# 02_CPU_1214c.net
KiCad netlist of a schematic drawn in Altium Designer
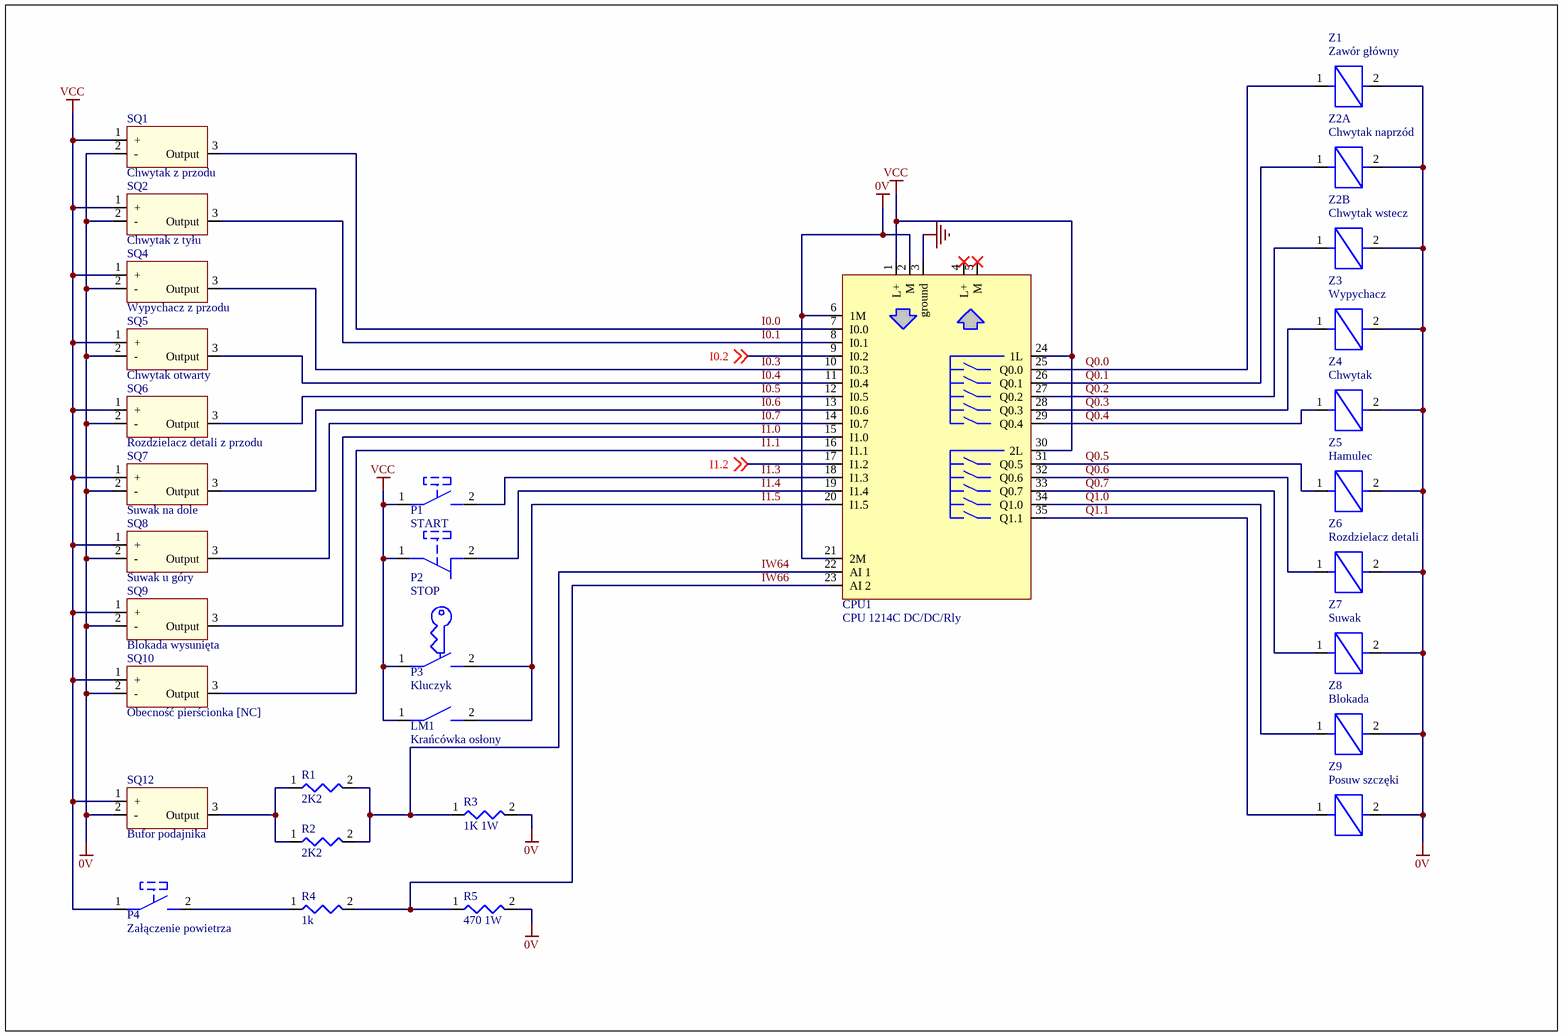
[diagram p0: [02] CPU 1214c.SchDoc]

(export (version "E")
  (design (tool "Eeschema 10.0.6"))
  (components
    (comp (ref "CPU1") (value "CPU 1214C DC/DC/Rly") (libsource (lib "Schlib2") (part "CPU 1214C DC/DC/Rly")))
    (comp (ref "LM1") (value "Krańcówka osłony") (libsource (lib "Schlib2") (part "NO")))
    (comp (ref "P1") (value "START") (libsource (lib "Schlib2") (part "Button NO")))
    (comp (ref "P2") (value "STOP") (libsource (lib "Schlib2") (part "Button NC")))
    (comp (ref "P3") (value "Kluczyk") (libsource (lib "Schlib2") (part "Key switch 1 line")))
    (comp (ref "P4") (value "Załączenie powietrza") (libsource (lib "Schlib2") (part "Button NO")))
    (comp (ref "R1") (value "2K2") (libsource (lib "Schlib2") (part "Resistor")))
    (comp (ref "R2") (value "2K2") (libsource (lib "Schlib2") (part "Resistor")))
    (comp (ref "R3") (value "1K 1W") (libsource (lib "Schlib2") (part "Resistor")))
    (comp (ref "R4") (value "1k") (libsource (lib "Schlib2") (part "Resistor")))
    (comp (ref "R5") (value "470 1W") (libsource (lib "Schlib2") (part "Resistor")))
    (comp (ref "SQ1") (value "Chwytak z przodu") (libsource (lib "Schlib2") (part "Magnetic sensor PNP")))
    (comp (ref "SQ2") (value "Chwytak z tyłu") (libsource (lib "Schlib2") (part "Magnetic sensor PNP")))
    (comp (ref "SQ4") (value "Wypychacz z przodu") (libsource (lib "Schlib2") (part "Magnetic sensor PNP")))
    (comp (ref "SQ5") (value "Chwytak otwarty") (libsource (lib "Schlib2") (part "Magnetic sensor PNP")))
    (comp (ref "SQ6")
      (value "Rozdzielacz detali z przodu")
      (libsource (lib "Schlib2") (part "Magnetic sensor PNP"))
    )
    (comp (ref "SQ7") (value "Suwak na dole") (libsource (lib "Schlib2") (part "Magnetic sensor PNP")))
    (comp (ref "SQ8") (value "Suwak u góry") (libsource (lib "Schlib2") (part "Magnetic sensor PNP")))
    (comp (ref "SQ9") (value "Blokada wysunięta") (libsource (lib "Schlib2") (part "Magnetic sensor PNP")))
    (comp (ref "SQ10")
      (value "Obecność pierścionka [NC]")
      (libsource (lib "Schlib2") (part "Magnetic sensor PNP"))
    )
    (comp (ref "SQ12") (value "Bufor podajnika") (libsource (lib "Schlib2") (part "Magnetic sensor PNP")))
    (comp (ref "Z1") (value "Zawór główny") (libsource (lib "Schlib2") (part "Coil")))
    (comp (ref "Z2A") (value "Chwytak naprzód") (libsource (lib "Schlib2") (part "Coil")))
    (comp (ref "Z2B") (value "Chwytak wstecz") (libsource (lib "Schlib2") (part "Coil")))
    (comp (ref "Z3") (value "Wypychacz") (libsource (lib "Schlib2") (part "Coil")))
    (comp (ref "Z4") (value "Chwytak") (libsource (lib "Schlib2") (part "Coil")))
    (comp (ref "Z5") (value "Hamulec") (libsource (lib "Schlib2") (part "Coil")))
    (comp (ref "Z6") (value "Rozdzielacz detali") (libsource (lib "Schlib2") (part "Coil")))
    (comp (ref "Z7") (value "Suwak") (libsource (lib "Schlib2") (part "Coil")))
    (comp (ref "Z8") (value "Blokada") (libsource (lib "Schlib2") (part "Coil")))
    (comp (ref "Z9") (value "Posuw szczęki") (libsource (lib "Schlib2") (part "Coil")))
  )
  (nets
    (net (code "1") (name "/I0.0") (class "Default")
      (node (ref "CPU1") (pin "7") (pinfunction "I0.0_7") (pintype "passive"))
      (node (ref "SQ1") (pin "3") (pinfunction "Output_3") (pintype "passive"))
    )
    (net (code "2") (name "/I0.1") (class "Default")
      (node (ref "CPU1") (pin "8") (pinfunction "I0.1_8") (pintype "passive"))
      (node (ref "SQ2") (pin "3") (pinfunction "Output_3") (pintype "passive"))
    )
    (net (code "3") (name "/I0.3") (class "Default")
      (node (ref "CPU1") (pin "10") (pinfunction "I0.3_10") (pintype "passive"))
      (node (ref "SQ4") (pin "3") (pinfunction "Output_3") (pintype "passive"))
    )
    (net (code "4") (name "/I0.4") (class "Default")
      (node (ref "CPU1") (pin "11") (pinfunction "I0.4_11") (pintype "passive"))
      (node (ref "SQ5") (pin "3") (pinfunction "Output_3") (pintype "passive"))
    )
    (net (code "5") (name "/I0.5") (class "Default")
      (node (ref "CPU1") (pin "12") (pinfunction "I0.5_12") (pintype "passive"))
      (node (ref "SQ6") (pin "3") (pinfunction "Output_3") (pintype "passive"))
    )
    (net (code "6") (name "/I0.6") (class "Default")
      (node (ref "CPU1") (pin "13") (pinfunction "I0.6_13") (pintype "passive"))
      (node (ref "SQ7") (pin "3") (pinfunction "Output_3") (pintype "passive"))
    )
    (net (code "7") (name "/I0.7") (class "Default")
      (node (ref "CPU1") (pin "14") (pinfunction "I0.7_14") (pintype "passive"))
      (node (ref "SQ8") (pin "3") (pinfunction "Output_3") (pintype "passive"))
    )
    (net (code "8") (name "/I1.0") (class "Default")
      (node (ref "CPU1") (pin "15") (pinfunction "I1.0_15") (pintype "passive"))
      (node (ref "SQ9") (pin "3") (pinfunction "Output_3") (pintype "passive"))
    )
    (net (code "9") (name "/I1.1") (class "Default")
      (node (ref "CPU1") (pin "16") (pinfunction "I1.1_16") (pintype "passive"))
      (node (ref "SQ10") (pin "3") (pinfunction "Output_3") (pintype "passive"))
    )
    (net (code "10") (name "/I1.3") (class "Default")
      (node (ref "CPU1") (pin "18") (pinfunction "I1.3_18") (pintype "passive"))
      (node (ref "P1") (pin "2") (pinfunction "*_2") (pintype "passive"))
    )
    (net (code "11") (name "/I1.4") (class "Default")
      (node (ref "CPU1") (pin "19") (pinfunction "I1.4_19") (pintype "passive"))
      (node (ref "P2") (pin "2") (pinfunction "*_2") (pintype "passive"))
    )
    (net (code "12") (name "/I1.5") (class "Default")
      (node (ref "CPU1") (pin "20") (pinfunction "I1.5_20") (pintype "passive"))
      (node (ref "LM1") (pin "2") (pinfunction "*_2") (pintype "passive"))
      (node (ref "P3") (pin "2") (pinfunction "*_2") (pintype "passive"))
    )
    (net (code "13") (name "/IW64") (class "Default")
      (node (ref "CPU1") (pin "22") (pinfunction "AI_1_22") (pintype "passive"))
      (node (ref "R1") (pin "2") (pinfunction "4_2") (pintype "passive"))
      (node (ref "R2") (pin "2") (pinfunction "4_2") (pintype "passive"))
      (node (ref "R3") (pin "1") (pinfunction "3_1") (pintype "passive"))
    )
    (net (code "14") (name "/IW66") (class "Default")
      (node (ref "CPU1") (pin "23") (pinfunction "AI_2_23") (pintype "passive"))
      (node (ref "R4") (pin "2") (pinfunction "4_2") (pintype "passive"))
      (node (ref "R5") (pin "1") (pinfunction "3_1") (pintype "passive"))
    )
    (net (code "15") (name "/Q0.0") (class "Default")
      (node (ref "CPU1") (pin "25") (pinfunction "Q0.0_25") (pintype "passive"))
      (node (ref "Z1") (pin "1") (pinfunction "*_1") (pintype "passive"))
    )
    (net (code "16") (name "/Q0.1") (class "Default")
      (node (ref "CPU1") (pin "26") (pinfunction "Q0.1_26") (pintype "passive"))
      (node (ref "Z2A") (pin "1") (pinfunction "*_1") (pintype "passive"))
    )
    (net (code "17") (name "/Q0.2") (class "Default")
      (node (ref "CPU1") (pin "27") (pinfunction "Q0.2_27") (pintype "passive"))
      (node (ref "Z2B") (pin "1") (pinfunction "*_1") (pintype "passive"))
    )
    (net (code "18") (name "/Q0.3") (class "Default")
      (node (ref "CPU1") (pin "28") (pinfunction "Q0.3_28") (pintype "passive"))
      (node (ref "Z3") (pin "1") (pinfunction "*_1") (pintype "passive"))
    )
    (net (code "19") (name "/Q0.4") (class "Default")
      (node (ref "CPU1") (pin "29") (pinfunction "Q0.4_29") (pintype "passive"))
      (node (ref "Z4") (pin "1") (pinfunction "*_1") (pintype "passive"))
    )
    (net (code "20") (name "/Q0.5") (class "Default")
      (node (ref "CPU1") (pin "31") (pinfunction "Q0.5_31") (pintype "passive"))
      (node (ref "Z5") (pin "1") (pinfunction "*_1") (pintype "passive"))
    )
    (net (code "21") (name "/Q0.6") (class "Default")
      (node (ref "CPU1") (pin "32") (pinfunction "Q0.6_32") (pintype "passive"))
      (node (ref "Z6") (pin "1") (pinfunction "*_1") (pintype "passive"))
    )
    (net (code "22") (name "/Q0.7") (class "Default")
      (node (ref "CPU1") (pin "33") (pinfunction "Q0.7_33") (pintype "passive"))
      (node (ref "Z7") (pin "1") (pinfunction "*_1") (pintype "passive"))
    )
    (net (code "23") (name "/Q1.0") (class "Default")
      (node (ref "CPU1") (pin "34") (pinfunction "Q1.0_34") (pintype "passive"))
      (node (ref "Z8") (pin "1") (pinfunction "*_1") (pintype "passive"))
    )
    (net (code "24") (name "/Q1.1") (class "Default")
      (node (ref "CPU1") (pin "35") (pinfunction "Q1.1_35") (pintype "passive"))
      (node (ref "Z9") (pin "1") (pinfunction "*_1") (pintype "passive"))
    )
    (net (code "25") (name "0V") (class "Default")
      (node (ref "CPU1") (pin "2") (pinfunction "M_2") (pintype "passive"))
      (node (ref "CPU1") (pin "21") (pinfunction "2M_21") (pintype "passive"))
      (node (ref "CPU1") (pin "6") (pinfunction "1M_6") (pintype "passive"))
      (node (ref "R3") (pin "2") (pinfunction "4_2") (pintype "passive"))
      (node (ref "R5") (pin "2") (pinfunction "4_2") (pintype "passive"))
      (node (ref "SQ1") (pin "2") (pinfunction "-_2") (pintype "passive"))
      (node (ref "SQ10") (pin "2") (pinfunction "-_2") (pintype "passive"))
      (node (ref "SQ12") (pin "2") (pinfunction "-_2") (pintype "passive"))
      (node (ref "SQ2") (pin "2") (pinfunction "-_2") (pintype "passive"))
      (node (ref "SQ4") (pin "2") (pinfunction "-_2") (pintype "passive"))
      (node (ref "SQ5") (pin "2") (pinfunction "-_2") (pintype "passive"))
      (node (ref "SQ6") (pin "2") (pinfunction "-_2") (pintype "passive"))
      (node (ref "SQ7") (pin "2") (pinfunction "-_2") (pintype "passive"))
      (node (ref "SQ8") (pin "2") (pinfunction "-_2") (pintype "passive"))
      (node (ref "SQ9") (pin "2") (pinfunction "-_2") (pintype "passive"))
      (node (ref "Z1") (pin "2") (pinfunction "*_2") (pintype "passive"))
      (node (ref "Z2A") (pin "2") (pinfunction "*_2") (pintype "passive"))
      (node (ref "Z2B") (pin "2") (pinfunction "*_2") (pintype "passive"))
      (node (ref "Z3") (pin "2") (pinfunction "*_2") (pintype "passive"))
      (node (ref "Z4") (pin "2") (pinfunction "*_2") (pintype "passive"))
      (node (ref "Z5") (pin "2") (pinfunction "*_2") (pintype "passive"))
      (node (ref "Z6") (pin "2") (pinfunction "*_2") (pintype "passive"))
      (node (ref "Z7") (pin "2") (pinfunction "*_2") (pintype "passive"))
      (node (ref "Z8") (pin "2") (pinfunction "*_2") (pintype "passive"))
      (node (ref "Z9") (pin "2") (pinfunction "*_2") (pintype "passive"))
    )
    (net (code "26") (name "GND") (class "Default")
      (node (ref "CPU1") (pin "3") (pinfunction "ground_3") (pintype "passive"))
    )
    (net (code "27") (name "I0.2") (class "Default")
      (node (ref "CPU1") (pin "9") (pinfunction "I0.2_9") (pintype "passive"))
    )
    (net (code "28") (name "I1.2") (class "Default")
      (node (ref "CPU1") (pin "17") (pinfunction "I1.2_17") (pintype "passive"))
    )
    (net (code "29") (name "Net-(R1-3)") (class "Default")
      (node (ref "R1") (pin "1") (pinfunction "3_1") (pintype "passive"))
      (node (ref "R2") (pin "1") (pinfunction "3_1") (pintype "passive"))
      (node (ref "SQ12") (pin "3") (pinfunction "Output_3") (pintype "passive"))
    )
    (net (code "30") (name "Net-(R4-3)") (class "Default")
      (node (ref "P4") (pin "2") (pinfunction "*_2") (pintype "passive"))
      (node (ref "R4") (pin "1") (pinfunction "3_1") (pintype "passive"))
    )
    (net (code "31") (name "VCC") (class "Default")
      (node (ref "CPU1") (pin "1") (pinfunction "L+_1") (pintype "passive"))
      (node (ref "CPU1") (pin "24") (pinfunction "1L_24") (pintype "passive"))
      (node (ref "CPU1") (pin "30") (pinfunction "2L_30") (pintype "passive"))
      (node (ref "LM1") (pin "1") (pinfunction "*_1") (pintype "passive"))
      (node (ref "P1") (pin "1") (pinfunction "*_1") (pintype "passive"))
      (node (ref "P2") (pin "1") (pinfunction "*_1") (pintype "passive"))
      (node (ref "P3") (pin "1") (pinfunction "*_1") (pintype "passive"))
      (node (ref "P4") (pin "1") (pinfunction "*_1") (pintype "passive"))
      (node (ref "SQ1") (pin "1") (pinfunction "+_1") (pintype "passive"))
      (node (ref "SQ10") (pin "1") (pinfunction "+_1") (pintype "passive"))
      (node (ref "SQ12") (pin "1") (pinfunction "+_1") (pintype "passive"))
      (node (ref "SQ2") (pin "1") (pinfunction "+_1") (pintype "passive"))
      (node (ref "SQ4") (pin "1") (pinfunction "+_1") (pintype "passive"))
      (node (ref "SQ5") (pin "1") (pinfunction "+_1") (pintype "passive"))
      (node (ref "SQ6") (pin "1") (pinfunction "+_1") (pintype "passive"))
      (node (ref "SQ7") (pin "1") (pinfunction "+_1") (pintype "passive"))
      (node (ref "SQ8") (pin "1") (pinfunction "+_1") (pintype "passive"))
      (node (ref "SQ9") (pin "1") (pinfunction "+_1") (pintype "passive"))
    )
    (net (code "32") (name "unconnected-(CPU1-L+-Pad4)") (class "Default")
      (node (ref "CPU1") (pin "4") (pinfunction "L+_4") (pintype "passive+no_connect"))
    )
    (net (code "33") (name "unconnected-(CPU1-M-Pad5)") (class "Default")
      (node (ref "CPU1") (pin "5") (pinfunction "M_5") (pintype "passive+no_connect"))
    )
  )
)
